# ST_LINK_V2-1.net
KiCad netlist of a schematic drawn in Altium Designer
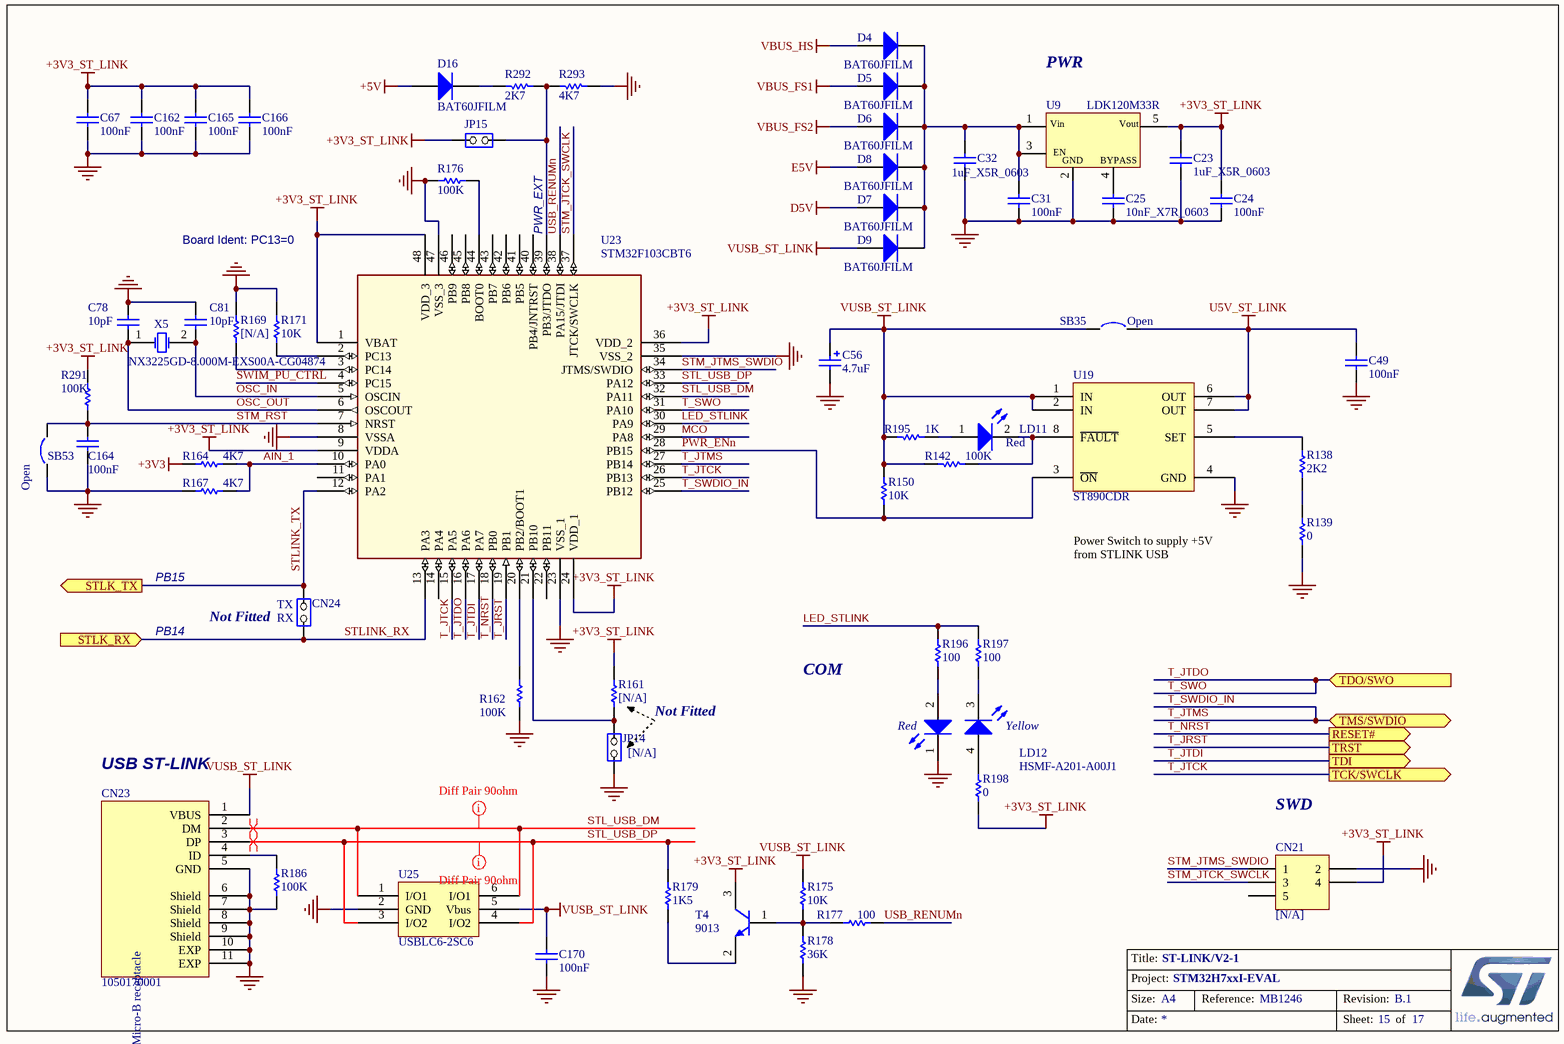
[diagram p0: ST_LINK_V2-1.SCHDOC]

(export (version "E")
  (design (tool "Eeschema 10.0.6"))
  (components
    (comp (ref "C23")
      (value "1uF_X5R_0603")
      (footprint "0603C")
      (description "0603  X5R 1µF")
      (fields (field (name "TOLERANCE") "10%"))
      (libsource (lib "MB963_1") (part "CAP SMD 0603  X5R 1µF 25V 10%"))
    )
    (comp (ref "C24")
      (value "100nF")
      (footprint "0603C")
      (description "Capacitor 0402 / 0603 / 0805")
      (libsource (lib "MCD_TOOLS") (part "Capacitor_ST"))
    )
    (comp (ref "C25")
      (value "10nF_X7R_0603")
      (footprint "0603C")
      (description "0603  X7R 10NF")
      (fields (field (name "TOLERANCE") "10%"))
      (libsource (lib "MB963_1") (part "CAP SMD 0603  X7R 10000PF 50V 10%"))
    )
    (comp (ref "C31")
      (value "100nF")
      (footprint "0603C")
      (description "Capacitor 0402 / 0603 / 0805")
      (libsource (lib "MCD_TOOLS") (part "Capacitor_ST"))
    )
    (comp (ref "C32")
      (value "1uF_X5R_0603")
      (footprint "0603C")
      (description "0603  X5R 1µF")
      (fields (field (name "TOLERANCE") "10%"))
      (libsource (lib "MB963_1") (part "CAP SMD 0603  X5R 1µF 25V 10%"))
    )
    (comp (ref "C49")
      (value "100nF")
      (footprint "0603C")
      (description "Capacitor 0402 / 0603 / 0805")
      (libsource (lib "MCD_TOOLS") (part "Capacitor_ST"))
    )
    (comp (ref "C56")
      (value "4.7uF")
      (footprint "TAN-A")
      (description "Polarized Capacitor (Radial)")
      (fields (field (name "PUBLISHER") "Altium Limited"))
      (libsource (lib "*") (part "Cap Pol1"))
    )
    (comp (ref "C67")
      (value "100nF")
      (footprint "0603C")
      (description "Capacitor 0402 / 0603 / 0805")
      (libsource (lib "MCD_TOOLS") (part "Capacitor_ST"))
    )
    (comp (ref "C78")
      (value "10pF")
      (footprint "0603C")
      (description "Capacitor 0402 / 0603 / 0805")
      (libsource (lib "MCD_TOOLS") (part "Capacitor_ST"))
    )
    (comp (ref "C81")
      (value "10pF")
      (footprint "0603C")
      (description "Capacitor 0402 / 0603 / 0805")
      (libsource (lib "MCD_TOOLS") (part "Capacitor_ST"))
    )
    (comp (ref "C162")
      (value "100nF")
      (footprint "0603C")
      (description "Capacitor 0402 / 0603 / 0805")
      (libsource (lib "MCD_TOOLS") (part "Capacitor_ST"))
    )
    (comp (ref "C164")
      (value "100nF")
      (footprint "0603C")
      (description "Capacitor 0402 / 0603 / 0805")
      (libsource (lib "MCD_TOOLS") (part "Capacitor_ST"))
    )
    (comp (ref "C165")
      (value "100nF")
      (footprint "0603C")
      (description "Capacitor 0402 / 0603 / 0805")
      (libsource (lib "MCD_TOOLS") (part "Capacitor_ST"))
    )
    (comp (ref "C166")
      (value "100nF")
      (footprint "0603C")
      (description "Capacitor 0402 / 0603 / 0805")
      (libsource (lib "MCD_TOOLS") (part "Capacitor_ST"))
    )
    (comp (ref "C170")
      (value "100nF")
      (footprint "0603C")
      (description "Capacitor 0402 / 0603 / 0805")
      (libsource (lib "MCD_TOOLS") (part "Capacitor_ST"))
    )
    (comp (ref "CN21")
      (value "[N/A]")
      (footprint "HDR_2X3-1_2R54-6")
      (description "Header, 3-Pin, Dual row")
      (fields (field (name "PUBLISHER") "Altium Limited"))
      (libsource (lib "Miscellaneous Connectors") (part "Header 3X2"))
    )
    (comp (ref "CN23")
      (value "1050170001")
      (footprint "MICRO_USB_B_105017")
      (libsource (lib "Smartphone_accessory") (part "1050170001"))
    )
    (comp (ref "CN24") (value "~") (footprint "SIP2") (libsource (lib "MCD_TOOLS") (part "JP2")))
    (comp (ref "D4")
      (value "BAT60JFILM")
      (footprint "SOD-323")
      (libsource (lib "MCD_TOOLS") (part "BAT60JFILM"))
    )
    (comp (ref "D5")
      (value "BAT60JFILM")
      (footprint "SOD-323")
      (libsource (lib "MCD_TOOLS") (part "BAT60JFILM"))
    )
    (comp (ref "D6")
      (value "BAT60JFILM")
      (footprint "SOD-323")
      (libsource (lib "MCD_TOOLS") (part "BAT60JFILM"))
    )
    (comp (ref "D7")
      (value "BAT60JFILM")
      (footprint "SOD-323")
      (libsource (lib "MCD_TOOLS") (part "BAT60JFILM"))
    )
    (comp (ref "D8")
      (value "BAT60JFILM")
      (footprint "SOD-323")
      (libsource (lib "MCD_TOOLS") (part "BAT60JFILM"))
    )
    (comp (ref "D9")
      (value "BAT60JFILM")
      (footprint "SOD-323")
      (libsource (lib "MCD_TOOLS") (part "BAT60JFILM"))
    )
    (comp (ref "D16")
      (value "BAT60JFILM")
      (footprint "SOD-323")
      (description "Default Diode")
      (fields (field (name "PUBLISHER") "Altium Limited"))
      (libsource (lib "MB1144_1") (part "Diode"))
    )
    (comp (ref "JP14") (value "[N/A]") (footprint "SIP2") (libsource (lib "*") (part "JP2")))
    (comp (ref "JP15") (value "~") (footprint "SIP2") (libsource (lib "*") (part "JP2")))
    (comp (ref "LD11")
      (value "Red")
      (footprint "0603D")
      (description "Typical RED, GREEN, YELLOW, AMBER GaAs LED")
      (fields (field (name "PUBLISHER") "Altium Limited"))
      (libsource (lib "Miscellaneous Devices") (part "LED2"))
    )
    (comp (ref "LD12")
      (value "HSMF-A201-A00J1")
      (footprint "LED2_3528")
      (libsource (lib "MB819") (part "HSMF-A201-A00J1"))
    )
    (comp (ref "R138")
      (value "2K2")
      (footprint "0402R")
      (description "Resistor 0402 or 0603 or 0805")
      (libsource (lib "MCD_TOOLS") (part "Resistor_ST"))
    )
    (comp (ref "R139")
      (value "0")
      (footprint "0603R")
      (description "Resistor")
      (fields (field (name "PUBLISHER") "Altium Limited"))
      (libsource (lib "") (part "Res1_2"))
    )
    (comp (ref "R142")
      (value "100K")
      (footprint "0603R")
      (description "Resistor")
      (fields (field (name "PUBLISHER") "Altium Limited"))
      (libsource (lib "*") (part "Res1"))
    )
    (comp (ref "R150")
      (value "10K")
      (footprint "0402R")
      (description "Resistor 0402 or 0603 or 0805")
      (libsource (lib "MCD_TOOLS") (part "Resistor_ST"))
    )
    (comp (ref "R161")
      (value "[N/A]")
      (footprint "0603R")
      (description "Resistor")
      (fields (field (name "PUBLISHER") "Altium Limited"))
      (libsource (lib "") (part "Res1_2"))
    )
    (comp (ref "R162")
      (value "100K")
      (footprint "0603R")
      (description "Resistor 0402 or 0603 or 0805")
      (libsource (lib "Miscellaneous Devices") (part "Res1"))
    )
    (comp (ref "R164")
      (value "4K7")
      (footprint "0603R")
      (description "Resistor 0402 or 0603 or 0805")
      (libsource (lib "Miscellaneous Devices") (part "Res1"))
    )
    (comp (ref "R167")
      (value "4K7")
      (footprint "0603R")
      (description "Resistor 0402 or 0603 or 0805")
      (libsource (lib "Miscellaneous Devices") (part "Res1"))
    )
    (comp (ref "R169")
      (value "[N/A]")
      (footprint "0603R")
      (description "Resistor 0402 or 0603 or 0805")
      (libsource (lib "Miscellaneous Devices") (part "Res1"))
    )
    (comp (ref "R171")
      (value "10K")
      (footprint "0603R")
      (description "Resistor 0402 or 0603 or 0805")
      (libsource (lib "Miscellaneous Devices") (part "Res1"))
    )
    (comp (ref "R175")
      (value "10K")
      (footprint "0603R")
      (description "Resistor")
      (fields (field (name "PUBLISHER") "Altium Limited"))
      (libsource (lib "") (part "Res1_2"))
    )
    (comp (ref "R176")
      (value "100K")
      (footprint "0603R")
      (description "Resistor 0402 or 0603 or 0805")
      (libsource (lib "Miscellaneous Devices") (part "Res1"))
    )
    (comp (ref "R177")
      (value "100")
      (footprint "0603R")
      (description "Resistor 0402 or 0603 or 0805")
      (libsource (lib "Miscellaneous Devices") (part "Res1"))
    )
    (comp (ref "R178")
      (value "36K")
      (footprint "0603R")
      (description "Resistor")
      (fields (field (name "PUBLISHER") "Altium Limited"))
      (libsource (lib "") (part "Res1_2"))
    )
    (comp (ref "R179")
      (value "1K5")
      (footprint "0603R")
      (description "Resistor 0402 or 0603 or 0805")
      (libsource (lib "Miscellaneous Devices") (part "Res1"))
    )
    (comp (ref "R186")
      (value "100K")
      (footprint "0603R")
      (description "Resistor 0402 or 0603 or 0805")
      (libsource (lib "Miscellaneous Devices") (part "Res1"))
    )
    (comp (ref "R195")
      (value "1K")
      (footprint "0603R")
      (description "Resistor")
      (fields (field (name "PUBLISHER") "Altium Limited"))
      (libsource (lib "*") (part "Res1"))
    )
    (comp (ref "R196")
      (value "100")
      (footprint "0603R")
      (description "Resistor")
      (fields (field (name "PUBLISHER") "Altium Limited"))
      (libsource (lib "") (part "Res1_2"))
    )
    (comp (ref "R197")
      (value "100")
      (footprint "0603R")
      (description "Resistor")
      (fields (field (name "PUBLISHER") "Altium Limited"))
      (libsource (lib "") (part "Res1_2"))
    )
    (comp (ref "R198")
      (value "0")
      (footprint "0603R")
      (description "Resistor")
      (fields (field (name "PUBLISHER") "Altium Limited"))
      (libsource (lib "") (part "Res1_2"))
    )
    (comp (ref "R291")
      (value "100K")
      (footprint "0603R")
      (description "Resistor 0402 or 0603 or 0805")
      (libsource (lib "Miscellaneous Devices") (part "Res1"))
    )
    (comp (ref "R292")
      (value "2K7")
      (footprint "0603R")
      (description "Resistor")
      (fields (field (name "PUBLISHER") "Altium Limited"))
      (libsource (lib "") (part "Res1_1"))
    )
    (comp (ref "R293")
      (value "4K7")
      (footprint "0603R")
      (description "Resistor")
      (fields (field (name "PUBLISHER") "Altium Limited"))
      (libsource (lib "") (part "Res1_1"))
    )
    (comp (ref "SB35")
      (value "Open")
      (footprint "SB_0603")
      (description "Circuit Breaker")
      (fields (field (name "PUBLISHER") "Altium Limited"))
      (libsource (lib "MB1165") (part "Circuit Breaker"))
    )
    (comp (ref "SB53")
      (value "Open")
      (footprint "SB_0603")
      (description "Circuit Breaker")
      (fields (field (name "PUBLISHER") "Altium Limited"))
      (libsource (lib "MB1165") (part "Circuit Breaker"))
    )
    (comp (ref "T4")
      (value "9013")
      (footprint "SOT-23")
      (description "NPN Bipolar Transistor")
      (fields (field (name "PUBLISHER") "Altium Limited"))
      (libsource (lib "MB1167") (part "NPN"))
    )
    (comp (ref "U9")
      (value "LDK120M33R")
      (footprint "SOT23-5")
      (description "Ultra low drop-low noise BiCMOS voltage, regulators low ESR capacitors compatible")
      (libsource (lib "MB1246") (part "LDK120M33R"))
    )
    (comp (ref "U19")
      (value "ST890CDR")
      (footprint "SOIC8_1R27_4R9X6")
      (libsource (lib "MB1167") (part "ST890CDR"))
    )
    (comp (ref "U23")
      (value "STM32F103CBT6")
      (footprint "LQFP48_0R5_9X9")
      (description "Medium-density performance line ARM-based 32-bit MCU with 64KB Flash")
      (libsource (lib "Nucleo_64") (part "STM32F103CBT6"))
    )
    (comp (ref "U25")
      (value "USBLC6-2SC6")
      (footprint "SOT23-6L")
      (libsource (lib "MB1137") (part "USBLC6-2SC6"))
    )
    (comp (ref "X5")
      (value "NX3225GD-8.000M-EXS00A-CG04874")
      (footprint "XTAL_2SM_3R2X2R5_H1")
      (description "Crystal Oscillator")
      (fields (field (name "PUBLISHER") "Altium Limited"))
      (libsource (lib "MB963_1") (part "XTAL"))
    )
  )
  (nets
    (net (code "1") (name "+3V3") (class "Default")
      (node (ref "R164") (pin "1") (pinfunction "1_1") (pintype "passive"))
    )
    (net (code "2") (name "+3V3_ST_LINK") (class "Default")
      (node (ref "C162") (pin "2") (pinfunction "2_2") (pintype "passive"))
      (node (ref "C165") (pin "2") (pinfunction "2_2") (pintype "passive"))
      (node (ref "C166") (pin "2") (pinfunction "2_2") (pintype "passive"))
      (node (ref "C23") (pin "1") (pinfunction "1_1") (pintype "passive"))
      (node (ref "C24") (pin "2") (pinfunction "2_2") (pintype "passive"))
      (node (ref "C67") (pin "2") (pinfunction "2_2") (pintype "passive"))
      (node (ref "CN21") (pin "4") (pinfunction "4_4") (pintype "passive"))
      (node (ref "JP15") (pin "1") (pinfunction "COMMON_1") (pintype "passive"))
      (node (ref "R161") (pin "1") (pinfunction "1_1") (pintype "passive"))
      (node (ref "R198") (pin "2") (pinfunction "2_2") (pintype "passive"))
      (node (ref "R291") (pin "2") (pinfunction "2_2") (pintype "passive"))
      (node (ref "T4") (pin "3") (pinfunction "C_3") (pintype "passive"))
      (node (ref "U23") (pin "1") (pinfunction "VBAT_1") (pintype "power_in"))
      (node (ref "U23") (pin "24") (pinfunction "VDD_1_24") (pintype "power_in"))
      (node (ref "U23") (pin "36") (pinfunction "VDD_2_36") (pintype "power_in"))
      (node (ref "U23") (pin "48") (pinfunction "VDD_3_48") (pintype "power_in"))
      (node (ref "U23") (pin "9") (pinfunction "VDDA_9") (pintype "power_in"))
      (node (ref "U9") (pin "5") (pinfunction "Vout_5") (pintype "passive"))
    )
    (net (code "3") (name "+5V") (class "Default")
      (node (ref "D16") (pin "1") (pinfunction "A_1") (pintype "passive"))
    )
    (net (code "4") (name "/AIN_1") (class "Default")
      (node (ref "R164") (pin "2") (pinfunction "2_2") (pintype "passive"))
      (node (ref "R167") (pin "2") (pinfunction "2_2") (pintype "passive"))
      (node (ref "U23") (pin "10") (pinfunction "PA0_10") (pintype "bidirectional"))
    )
    (net (code "5") (name "/LED_STLINK") (class "Default")
      (node (ref "R196") (pin "1") (pinfunction "1_1") (pintype "passive"))
      (node (ref "R197") (pin "1") (pinfunction "1_1") (pintype "passive"))
      (node (ref "U23") (pin "30") (pinfunction "PA9_30") (pintype "bidirectional"))
    )
    (net (code "6") (name "/MCO") (class "Default")
      (node (ref "U23") (pin "29") (pinfunction "PA8_29") (pintype "bidirectional"))
    )
    (net (code "7") (name "/OSC_IN") (class "Default")
      (node (ref "C81") (pin "1") (pinfunction "1_1") (pintype "passive"))
      (node (ref "U23") (pin "5") (pinfunction "OSCIN_5") (pintype "input"))
      (node (ref "X5") (pin "2") (pinfunction "OSC2_2") (pintype "passive"))
    )
    (net (code "8") (name "/OSC_OUT") (class "Default")
      (node (ref "C78") (pin "1") (pinfunction "1_1") (pintype "passive"))
      (node (ref "U23") (pin "6") (pinfunction "OSCOUT_6") (pintype "output"))
      (node (ref "X5") (pin "1") (pinfunction "OSC1_1") (pintype "passive"))
    )
    (net (code "9") (name "/PWR_ENn") (class "Default")
      (node (ref "R150") (pin "2") (pinfunction "2_2") (pintype "passive"))
      (node (ref "U19") (pin "3") (pinfunction "~{ON}_3") (pintype "passive"))
      (node (ref "U23") (pin "28") (pinfunction "PB15_28") (pintype "bidirectional"))
    )
    (net (code "10") (name "/STLINK_RX") (class "Default")
      (node (ref "CN24") (pin "1") (pinfunction "COMMON_1") (pintype "passive"))
      (node (ref "U23") (pin "13") (pinfunction "PA3_13") (pintype "bidirectional"))
    )
    (net (code "11") (name "/STLINK_TX") (class "Default")
      (node (ref "CN24") (pin "2") (pinfunction "NO_2") (pintype "passive"))
      (node (ref "U23") (pin "12") (pinfunction "PA2_12") (pintype "bidirectional"))
    )
    (net (code "12") (name "/STL_USB_DM") (class "Default")
      (node (ref "CN23") (pin "2") (pinfunction "DM_2") (pintype "passive"))
      (node (ref "U23") (pin "32") (pinfunction "PA11_32") (pintype "bidirectional"))
      (node (ref "U25") (pin "1") (pinfunction "I/O1_1") (pintype "passive"))
      (node (ref "U25") (pin "6") (pinfunction "I/O1_6") (pintype "passive"))
    )
    (net (code "13") (name "/STL_USB_DP") (class "Default")
      (node (ref "CN23") (pin "3") (pinfunction "DP_3") (pintype "passive"))
      (node (ref "R179") (pin "1") (pinfunction "1_1") (pintype "passive"))
      (node (ref "U23") (pin "33") (pinfunction "PA12_33") (pintype "bidirectional"))
      (node (ref "U25") (pin "3") (pinfunction "I/O2_3") (pintype "passive"))
      (node (ref "U25") (pin "4") (pinfunction "I/O2_4") (pintype "passive"))
    )
    (net (code "14") (name "/STM_JTCK_SWCLK") (class "Default")
      (node (ref "CN21") (pin "3") (pinfunction "3_3") (pintype "passive"))
      (node (ref "U23") (pin "37") (pinfunction "JTCK/SWCLK_37") (pintype "bidirectional"))
    )
    (net (code "15") (name "/STM_JTMS_SWDIO") (class "Default")
      (node (ref "CN21") (pin "1") (pinfunction "1_1") (pintype "passive"))
      (node (ref "U23") (pin "34") (pinfunction "JTMS/SWDIO_34") (pintype "bidirectional"))
    )
    (net (code "16") (name "/STM_RST") (class "Default")
      (node (ref "C164") (pin "2") (pinfunction "2_2") (pintype "passive"))
      (node (ref "R291") (pin "1") (pinfunction "1_1") (pintype "passive"))
      (node (ref "SB53") (pin "2") (pinfunction "2_2") (pintype "passive"))
      (node (ref "U23") (pin "7") (pinfunction "NRST_7") (pintype "input"))
    )
    (net (code "17") (name "/SWIM_PU_CTRL") (class "Default")
      (node (ref "U23") (pin "4") (pinfunction "PC15_4") (pintype "bidirectional"))
    )
    (net (code "18") (name "/T_JRST") (class "Default")
      (node (ref "U23") (pin "19") (pinfunction "PB1_19") (pintype "input"))
    )
    (net (code "19") (name "/T_JTCK") (class "Default")
      (node (ref "U23") (pin "15") (pinfunction "PA5_15") (pintype "bidirectional"))
      (node (ref "U23") (pin "26") (pinfunction "PB13_26") (pintype "bidirectional"))
    )
    (net (code "20") (name "/T_JTDI") (class "Default")
      (node (ref "U23") (pin "17") (pinfunction "PA7_17") (pintype "bidirectional"))
    )
    (net (code "21") (name "/T_JTDO") (class "Default")
      (node (ref "U23") (pin "16") (pinfunction "PA6_16") (pintype "bidirectional"))
      (node (ref "U23") (pin "31") (pinfunction "PA10_31") (pintype "bidirectional"))
    )
    (net (code "22") (name "/T_JTMS") (class "Default")
      (node (ref "U23") (pin "25") (pinfunction "PB12_25") (pintype "bidirectional"))
      (node (ref "U23") (pin "27") (pinfunction "PB14_27") (pintype "bidirectional"))
    )
    (net (code "23") (name "/T_NRST") (class "Default")
      (node (ref "U23") (pin "18") (pinfunction "PB0_18") (pintype "bidirectional"))
    )
    (net (code "24") (name "/USB_RENUMn") (class "Default")
      (node (ref "R177") (pin "2") (pinfunction "2_2") (pintype "passive"))
      (node (ref "U23") (pin "38") (pinfunction "PA15/JTDI_38") (pintype "bidirectional"))
    )
    (net (code "25") (name "D5V") (class "Default")
      (node (ref "D7") (pin "1") (pinfunction "A_1") (pintype "passive"))
    )
    (net (code "26") (name "E5V") (class "Default")
      (node (ref "D8") (pin "1") (pinfunction "A_1") (pintype "passive"))
    )
    (net (code "27") (name "GND") (class "Default")
      (node (ref "C162") (pin "1") (pinfunction "1_1") (pintype "passive"))
      (node (ref "C164") (pin "1") (pinfunction "1_1") (pintype "passive"))
      (node (ref "C165") (pin "1") (pinfunction "1_1") (pintype "passive"))
      (node (ref "C166") (pin "1") (pinfunction "1_1") (pintype "passive"))
      (node (ref "C170") (pin "1") (pinfunction "1_1") (pintype "passive"))
      (node (ref "C23") (pin "2") (pinfunction "2_2") (pintype "passive"))
      (node (ref "C24") (pin "1") (pinfunction "1_1") (pintype "passive"))
      (node (ref "C25") (pin "1") (pinfunction "1_1") (pintype "passive"))
      (node (ref "C31") (pin "1") (pinfunction "1_1") (pintype "passive"))
      (node (ref "C32") (pin "1") (pinfunction "1_1") (pintype "passive"))
      (node (ref "C49") (pin "1") (pinfunction "1_1") (pintype "passive"))
      (node (ref "C56") (pin "2") (pinfunction "2_2") (pintype "passive"))
      (node (ref "C67") (pin "1") (pinfunction "1_1") (pintype "passive"))
      (node (ref "C78") (pin "2") (pinfunction "2_2") (pintype "passive"))
      (node (ref "C81") (pin "2") (pinfunction "2_2") (pintype "passive"))
      (node (ref "CN21") (pin "2") (pinfunction "2_2") (pintype "passive"))
      (node (ref "CN23") (pin "10") (pinfunction "EXP_10") (pintype "passive"))
      (node (ref "CN23") (pin "11") (pinfunction "EXP_11") (pintype "passive"))
      (node (ref "CN23") (pin "5") (pinfunction "GND_5") (pintype "passive"))
      (node (ref "CN23") (pin "6") (pinfunction "Shield_6") (pintype "passive"))
      (node (ref "CN23") (pin "7") (pinfunction "Shield_7") (pintype "passive"))
      (node (ref "CN23") (pin "8") (pinfunction "Shield_8") (pintype "passive"))
      (node (ref "CN23") (pin "9") (pinfunction "Shield_9") (pintype "passive"))
      (node (ref "JP14") (pin "1") (pinfunction "COMMON_1") (pintype "passive"))
      (node (ref "LD12") (pin "1") (pinfunction "RED_cathode_1") (pintype "passive"))
      (node (ref "R139") (pin "1") (pinfunction "1_1") (pintype "passive"))
      (node (ref "R162") (pin "1") (pinfunction "1_1") (pintype "passive"))
      (node (ref "R167") (pin "1") (pinfunction "1_1") (pintype "passive"))
      (node (ref "R169") (pin "1") (pinfunction "1_1") (pintype "passive"))
      (node (ref "R171") (pin "1") (pinfunction "1_1") (pintype "passive"))
      (node (ref "R176") (pin "1") (pinfunction "1_1") (pintype "passive"))
      (node (ref "R178") (pin "1") (pinfunction "1_1") (pintype "passive"))
      (node (ref "R186") (pin "2") (pinfunction "2_2") (pintype "passive"))
      (node (ref "R293") (pin "2") (pinfunction "2_2") (pintype "passive"))
      (node (ref "SB53") (pin "1") (pinfunction "1_1") (pintype "passive"))
      (node (ref "U19") (pin "4") (pinfunction "GND_4") (pintype "passive"))
      (node (ref "U23") (pin "23") (pinfunction "VSS_1_23") (pintype "power_in"))
      (node (ref "U23") (pin "35") (pinfunction "VSS_2_35") (pintype "power_in"))
      (node (ref "U23") (pin "47") (pinfunction "VSS_3_47") (pintype "power_in"))
      (node (ref "U23") (pin "8") (pinfunction "VSSA_8") (pintype "power_in"))
      (node (ref "U25") (pin "2") (pinfunction "GND_2") (pintype "passive"))
      (node (ref "U9") (pin "2") (pinfunction "GND_2") (pintype "passive"))
    )
    (net (code "28") (name "Net-(CN23-ID)") (class "Default")
      (node (ref "CN23") (pin "4") (pinfunction "ID_4") (pintype "passive"))
      (node (ref "R186") (pin "1") (pinfunction "1_1") (pintype "passive"))
    )
    (net (code "29") (name "Net-(D4-K)") (class "Default")
      (node (ref "C31") (pin "2") (pinfunction "2_2") (pintype "passive"))
      (node (ref "C32") (pin "2") (pinfunction "2_2") (pintype "passive"))
      (node (ref "D4") (pin "2") (pinfunction "K_2") (pintype "passive"))
      (node (ref "D5") (pin "2") (pinfunction "K_2") (pintype "passive"))
      (node (ref "D6") (pin "2") (pinfunction "K_2") (pintype "passive"))
      (node (ref "D7") (pin "2") (pinfunction "K_2") (pintype "passive"))
      (node (ref "D8") (pin "2") (pinfunction "K_2") (pintype "passive"))
      (node (ref "D9") (pin "2") (pinfunction "K_2") (pintype "passive"))
      (node (ref "U9") (pin "1") (pinfunction "Vin_1") (pintype "passive"))
      (node (ref "U9") (pin "3") (pinfunction "CE_3") (pintype "passive"))
    )
    (net (code "30") (name "Net-(D16-K)") (class "Default")
      (node (ref "D16") (pin "2") (pinfunction "K_2") (pintype "passive"))
      (node (ref "R292") (pin "1") (pinfunction "1_1") (pintype "passive"))
    )
    (net (code "31") (name "Net-(JP14-NO)") (class "Default")
      (node (ref "JP14") (pin "2") (pinfunction "NO_2") (pintype "passive"))
      (node (ref "R161") (pin "2") (pinfunction "2_2") (pintype "passive"))
      (node (ref "U23") (pin "21") (pinfunction "PB10_21") (pintype "bidirectional"))
    )
    (net (code "32") (name "Net-(JP15-NO)") (class "Default")
      (node (ref "JP15") (pin "2") (pinfunction "NO_2") (pintype "passive"))
      (node (ref "R292") (pin "2") (pinfunction "2_2") (pintype "passive"))
      (node (ref "R293") (pin "1") (pinfunction "1_1") (pintype "passive"))
      (node (ref "U23") (pin "39") (pinfunction "PB3/JTDO_39") (pintype "bidirectional"))
    )
    (net (code "33") (name "Net-(LD11-A)") (class "Default")
      (node (ref "LD11") (pin "1") (pinfunction "A_1") (pintype "passive"))
      (node (ref "R195") (pin "2") (pinfunction "2_2") (pintype "passive"))
    )
    (net (code "34") (name "Net-(LD11-K)") (class "Default")
      (node (ref "LD11") (pin "2") (pinfunction "K_2") (pintype "passive"))
      (node (ref "R142") (pin "2") (pinfunction "2_2") (pintype "passive"))
      (node (ref "U19") (pin "8") (pinfunction "~{FAULT}_8") (pintype "passive"))
    )
    (net (code "35") (name "Net-(LD12-Red_anode)") (class "Default")
      (node (ref "LD12") (pin "2") (pinfunction "Red_anode_2") (pintype "passive"))
      (node (ref "R196") (pin "2") (pinfunction "2_2") (pintype "passive"))
    )
    (net (code "36") (name "Net-(LD12-YellowGreen_anode)") (class "Default")
      (node (ref "LD12") (pin "4") (pinfunction "YellowGreen_anode_4") (pintype "passive"))
      (node (ref "R198") (pin "1") (pinfunction "1_1") (pintype "passive"))
    )
    (net (code "37") (name "Net-(LD12-YellowGreen_cathode)") (class "Default")
      (node (ref "LD12") (pin "3") (pinfunction "YellowGreen_cathode_3") (pintype "passive"))
      (node (ref "R197") (pin "2") (pinfunction "2_2") (pintype "passive"))
    )
    (net (code "38") (name "Net-(R138-Pad1)") (class "Default")
      (node (ref "R138") (pin "1") (pinfunction "1_1") (pintype "passive"))
      (node (ref "R139") (pin "2") (pinfunction "2_2") (pintype "passive"))
    )
    (net (code "39") (name "Net-(T4-B)") (class "Default")
      (node (ref "R175") (pin "1") (pinfunction "1_1") (pintype "passive"))
      (node (ref "R177") (pin "1") (pinfunction "1_1") (pintype "passive"))
      (node (ref "R178") (pin "2") (pinfunction "2_2") (pintype "passive"))
      (node (ref "T4") (pin "1") (pinfunction "B_1") (pintype "passive"))
    )
    (net (code "40") (name "Net-(T4-E)") (class "Default")
      (node (ref "R179") (pin "2") (pinfunction "2_2") (pintype "passive"))
      (node (ref "T4") (pin "2") (pinfunction "E_2") (pintype "passive"))
    )
    (net (code "41") (name "Net-(U9-BYPASS)") (class "Default")
      (node (ref "C25") (pin "2") (pinfunction "2_2") (pintype "passive"))
      (node (ref "U9") (pin "4") (pinfunction "BYPASS_4") (pintype "passive"))
    )
    (net (code "42") (name "Net-(U19-SET)") (class "Default")
      (node (ref "R138") (pin "2") (pinfunction "2_2") (pintype "passive"))
      (node (ref "U19") (pin "5") (pinfunction "SET_5") (pintype "passive"))
    )
    (net (code "43") (name "Net-(U23-BOOT0)") (class "Default")
      (node (ref "R176") (pin "2") (pinfunction "2_2") (pintype "passive"))
      (node (ref "U23") (pin "44") (pinfunction "BOOT0_44") (pintype "bidirectional"))
    )
    (net (code "44") (name "Net-(U23-PB2{slash}BOOT1)") (class "Default")
      (node (ref "R162") (pin "2") (pinfunction "2_2") (pintype "passive"))
      (node (ref "U23") (pin "20") (pinfunction "PB2/BOOT1_20") (pintype "bidirectional"))
    )
    (net (code "45") (name "Net-(U23-PC13)") (class "Default")
      (node (ref "R171") (pin "2") (pinfunction "2_2") (pintype "passive"))
      (node (ref "U23") (pin "2") (pinfunction "PC13_2") (pintype "bidirectional"))
    )
    (net (code "46") (name "Net-(U23-PC14)") (class "Default")
      (node (ref "R169") (pin "2") (pinfunction "2_2") (pintype "passive"))
      (node (ref "U23") (pin "3") (pinfunction "PC14_3") (pintype "bidirectional"))
    )
    (net (code "47") (name "U5V_ST_LINK") (class "Default")
      (node (ref "C49") (pin "2") (pinfunction "2_2") (pintype "passive"))
      (node (ref "SB35") (pin "2") (pinfunction "2_2") (pintype "passive"))
      (node (ref "U19") (pin "6") (pinfunction "OUT_6") (pintype "passive"))
      (node (ref "U19") (pin "7") (pinfunction "OUT_7") (pintype "passive"))
    )
    (net (code "48") (name "VBUS_FS1") (class "Default")
      (node (ref "D5") (pin "1") (pinfunction "A_1") (pintype "passive"))
    )
    (net (code "49") (name "VBUS_FS2") (class "Default")
      (node (ref "D6") (pin "1") (pinfunction "A_1") (pintype "passive"))
    )
    (net (code "50") (name "VBUS_HS") (class "Default")
      (node (ref "D4") (pin "1") (pinfunction "A_1") (pintype "passive"))
    )
    (net (code "51") (name "VUSB_ST_LINK") (class "Default")
      (node (ref "C170") (pin "2") (pinfunction "2_2") (pintype "passive"))
      (node (ref "C56") (pin "1") (pinfunction "1_1") (pintype "passive"))
      (node (ref "CN23") (pin "1") (pinfunction "VBUS_1") (pintype "passive"))
      (node (ref "D9") (pin "1") (pinfunction "A_1") (pintype "passive"))
      (node (ref "R142") (pin "1") (pinfunction "1_1") (pintype "passive"))
      (node (ref "R150") (pin "1") (pinfunction "1_1") (pintype "passive"))
      (node (ref "R175") (pin "2") (pinfunction "2_2") (pintype "passive"))
      (node (ref "R195") (pin "1") (pinfunction "1_1") (pintype "passive"))
      (node (ref "SB35") (pin "1") (pinfunction "1_1") (pintype "passive"))
      (node (ref "U19") (pin "1") (pinfunction "IN_1") (pintype "passive"))
      (node (ref "U19") (pin "2") (pinfunction "IN_2") (pintype "passive"))
      (node (ref "U25") (pin "5") (pinfunction "Vbus_5") (pintype "passive"))
    )
    (net (code "52") (name "unconnected-(CN21-Pad5)") (class "Default")
      (node (ref "CN21") (pin "5") (pinfunction "5_5") (pintype "passive"))
    )
    (net (code "53") (name "unconnected-(U23-PA1-Pad11)") (class "Default")
      (node (ref "U23") (pin "11") (pinfunction "PA1_11") (pintype "bidirectional"))
    )
    (net (code "54") (name "unconnected-(U23-PA4-Pad14)") (class "Default")
      (node (ref "U23") (pin "14") (pinfunction "PA4_14") (pintype "bidirectional"))
    )
    (net (code "55") (name "unconnected-(U23-PB4{slash}JNTRST-Pad40)") (class "Default")
      (node (ref "U23") (pin "40") (pinfunction "PB4/JNTRST_40") (pintype "bidirectional"))
    )
    (net (code "56") (name "unconnected-(U23-PB5-Pad41)") (class "Default")
      (node (ref "U23") (pin "41") (pinfunction "PB5_41") (pintype "bidirectional"))
    )
    (net (code "57") (name "unconnected-(U23-PB6-Pad42)") (class "Default")
      (node (ref "U23") (pin "42") (pinfunction "PB6_42") (pintype "bidirectional"))
    )
    (net (code "58") (name "unconnected-(U23-PB7-Pad43)") (class "Default")
      (node (ref "U23") (pin "43") (pinfunction "PB7_43") (pintype "bidirectional"))
    )
    (net (code "59") (name "unconnected-(U23-PB8-Pad45)") (class "Default")
      (node (ref "U23") (pin "45") (pinfunction "PB8_45") (pintype "bidirectional"))
    )
    (net (code "60") (name "unconnected-(U23-PB9-Pad46)") (class "Default")
      (node (ref "U23") (pin "46") (pinfunction "PB9_46") (pintype "bidirectional"))
    )
    (net (code "61") (name "unconnected-(U23-PB11-Pad22)") (class "Default")
      (node (ref "U23") (pin "22") (pinfunction "PB11_22") (pintype "bidirectional"))
    )
  )
)
